# ChairControlInterceptor.net
KiCad netlist of a schematic drawn in EAGLE
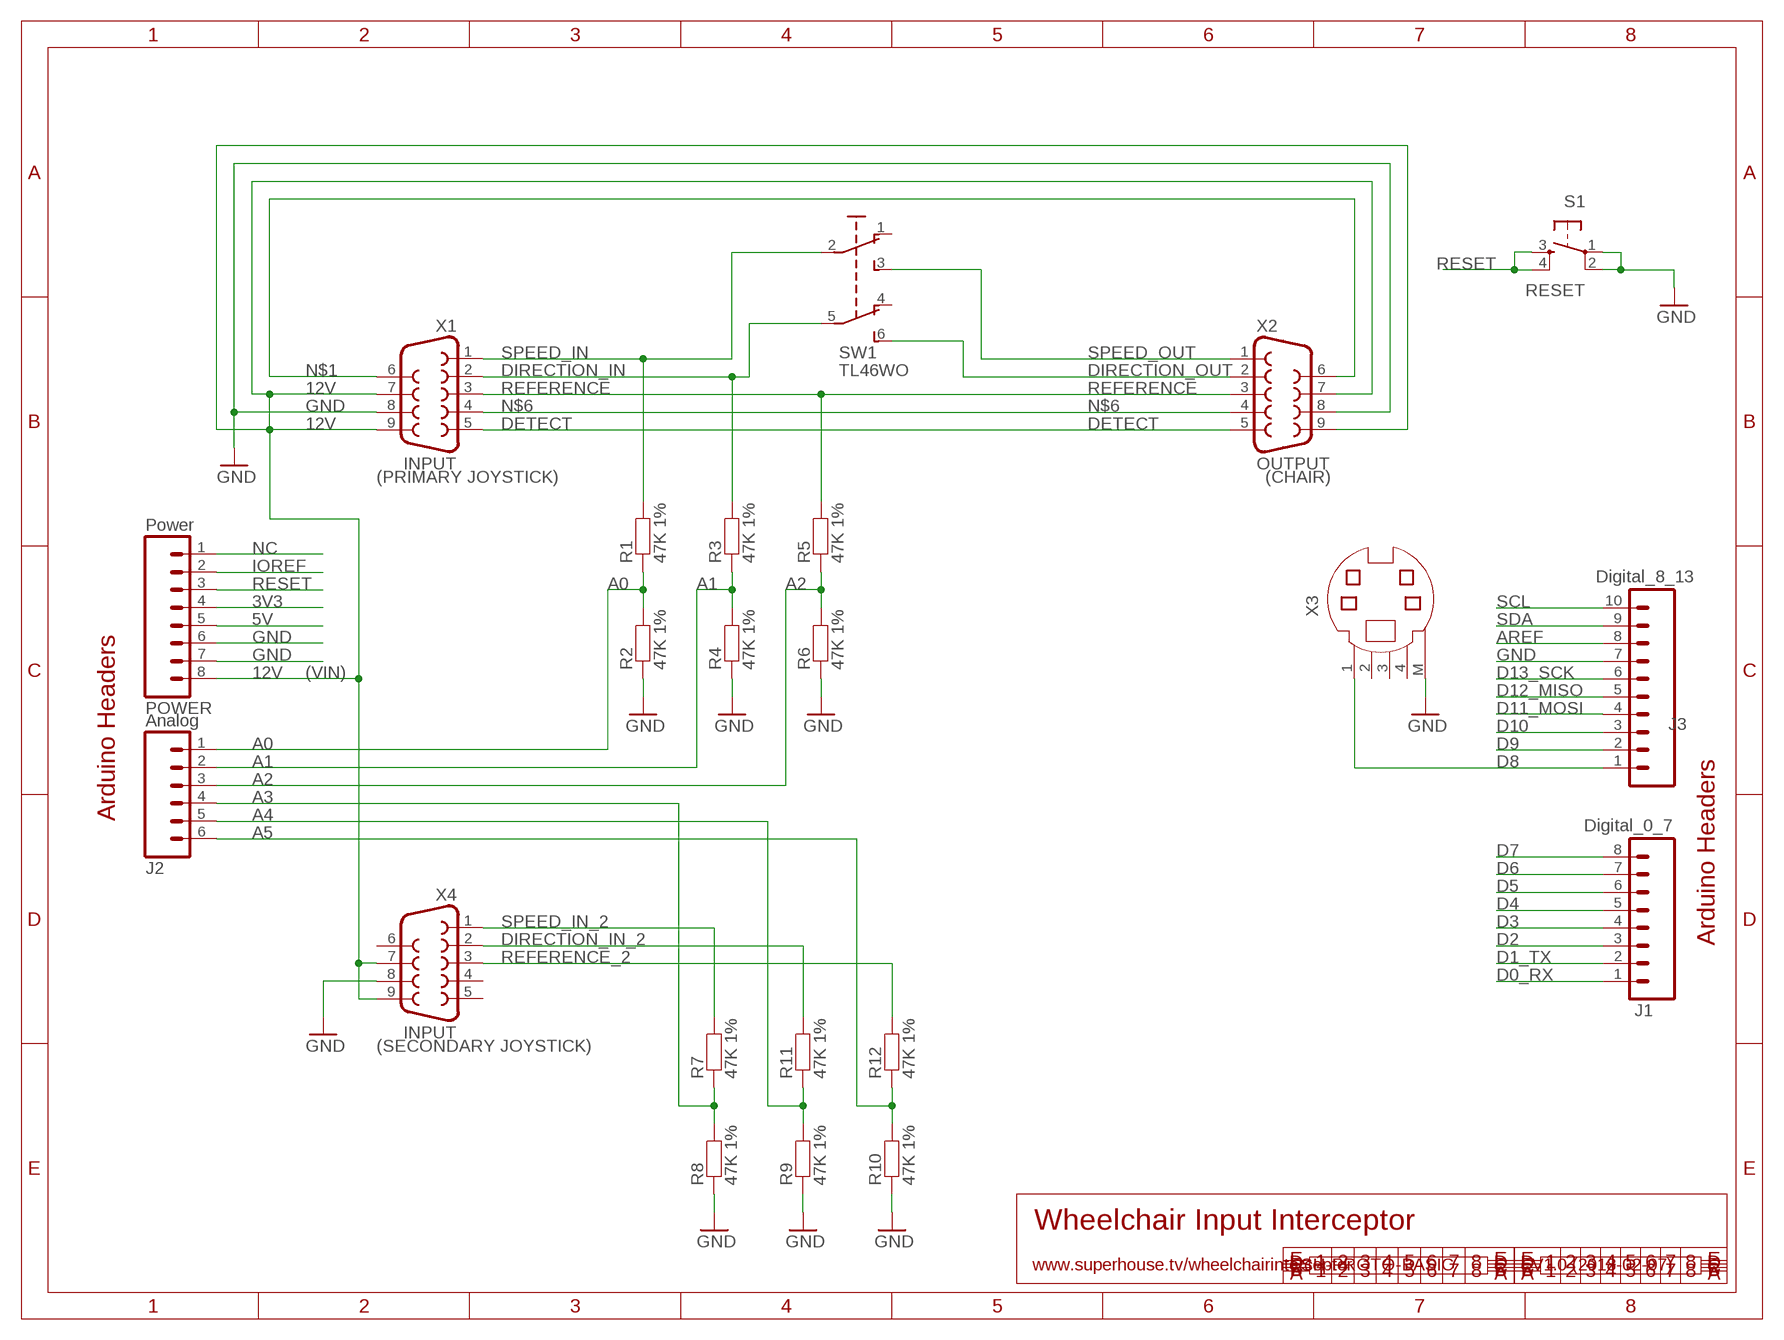
[diagram p0: schematic, sheet 1]

(export (version "E")
  (design (tool "Eeschema 10.0.6"))
  (components
    (comp (ref "J1")
      (value "Digital_0_7")
      (footprint "eagle-import:1X08")
      (libsource (lib "eagle-import") (part "M08"))
    )
    (comp (ref "J2")
      (value "Analog")
      (footprint "eagle-import:1X06")
      (libsource (lib "eagle-import") (part "M06SIP"))
    )
    (comp (ref "J3")
      (value "Digital_8_13")
      (footprint "eagle-import:1X10")
      (libsource (lib "eagle-import") (part "M100.1"))
    )
    (comp (ref "POWER")
      (value "Power")
      (footprint "eagle-import:1X08")
      (libsource (lib "eagle-import") (part "freetronics-original_M08"))
    )
    (comp (ref "R1")
      (value "47K 1%")
      (footprint "eagle-import:0603")
      (libsource (lib "eagle-import") (part "RESISTOR0603"))
    )
    (comp (ref "R2")
      (value "47K 1%")
      (footprint "eagle-import:0603")
      (libsource (lib "eagle-import") (part "RESISTOR0603"))
    )
    (comp (ref "R3")
      (value "47K 1%")
      (footprint "eagle-import:0603")
      (libsource (lib "eagle-import") (part "RESISTOR0603"))
    )
    (comp (ref "R4")
      (value "47K 1%")
      (footprint "eagle-import:0603")
      (libsource (lib "eagle-import") (part "RESISTOR0603"))
    )
    (comp (ref "R5")
      (value "47K 1%")
      (footprint "eagle-import:0603")
      (libsource (lib "eagle-import") (part "RESISTOR0603"))
    )
    (comp (ref "R6")
      (value "47K 1%")
      (footprint "eagle-import:0603")
      (libsource (lib "eagle-import") (part "RESISTOR0603"))
    )
    (comp (ref "R7")
      (value "47K 1%")
      (footprint "eagle-import:0603")
      (libsource (lib "eagle-import") (part "RESISTOR0603"))
    )
    (comp (ref "R8")
      (value "47K 1%")
      (footprint "eagle-import:0603")
      (libsource (lib "eagle-import") (part "RESISTOR0603"))
    )
    (comp (ref "R9")
      (value "47K 1%")
      (footprint "eagle-import:0603")
      (libsource (lib "eagle-import") (part "RESISTOR0603"))
    )
    (comp (ref "R10")
      (value "47K 1%")
      (footprint "eagle-import:0603")
      (libsource (lib "eagle-import") (part "RESISTOR0603"))
    )
    (comp (ref "R11")
      (value "47K 1%")
      (footprint "eagle-import:0603")
      (libsource (lib "eagle-import") (part "RESISTOR0603"))
    )
    (comp (ref "R12")
      (value "47K 1%")
      (footprint "eagle-import:0603")
      (libsource (lib "eagle-import") (part "RESISTOR0603"))
    )
    (comp (ref "S1")
      (value "RESET")
      (footprint "eagle-import:TACTILE-PTH")
      (libsource (lib "eagle-import") (part "TAC_SWITCHPTH"))
    )
    (comp (ref "SW1")
      (value "TL46WO")
      (footprint "eagle-import:TL4XWO")
      (libsource (lib "eagle-import") (part "TL46WO"))
    )
    (comp (ref "X1")
      (value "INPUT")
      (footprint "eagle-import:DB9_MALE")
      (libsource (lib "eagle-import") (part "DB9MALE"))
    )
    (comp (ref "X2")
      (value "OUTPUT")
      (footprint "eagle-import:DB9")
      (libsource (lib "eagle-import") (part "DB9FEMALE"))
    )
    (comp (ref "X3")
      (value "MD04S")
      (footprint "eagle-import:MDIN04S")
      (libsource (lib "eagle-import") (part "MD04S"))
    )
    (comp (ref "X4")
      (value "INPUT")
      (footprint "eagle-import:DB9_MALE")
      (libsource (lib "eagle-import") (part "DB9MALE"))
    )
  )
  (nets
    (net (code "1") (name "/3V3") (class "Default")
      (node (ref "POWER") (pin "4") (pinfunction "4_4") (pintype "passive"))
    )
    (net (code "2") (name "/5V") (class "Default")
      (node (ref "POWER") (pin "5") (pinfunction "5_5") (pintype "passive"))
    )
    (net (code "3") (name "/12V") (class "Default")
      (node (ref "POWER") (pin "8") (pinfunction "8_8") (pintype "passive"))
      (node (ref "X1") (pin "7") (pinfunction "7_7") (pintype "passive"))
      (node (ref "X1") (pin "9") (pinfunction "9_9") (pintype "passive"))
      (node (ref "X2") (pin "7") (pinfunction "7_7") (pintype "passive"))
      (node (ref "X2") (pin "9") (pinfunction "9_9") (pintype "passive"))
      (node (ref "X4") (pin "7") (pinfunction "7_7") (pintype "passive"))
      (node (ref "X4") (pin "9") (pinfunction "9_9") (pintype "passive"))
    )
    (net (code "4") (name "/A0") (class "Default")
      (node (ref "J2") (pin "1") (pinfunction "1_1") (pintype "passive"))
      (node (ref "R1") (pin "1") (pinfunction "1_1") (pintype "passive"))
      (node (ref "R2") (pin "2") (pinfunction "2_2") (pintype "passive"))
    )
    (net (code "5") (name "/A1") (class "Default")
      (node (ref "J2") (pin "2") (pinfunction "2_2") (pintype "passive"))
      (node (ref "R3") (pin "1") (pinfunction "1_1") (pintype "passive"))
      (node (ref "R4") (pin "2") (pinfunction "2_2") (pintype "passive"))
    )
    (net (code "6") (name "/A2") (class "Default")
      (node (ref "J2") (pin "3") (pinfunction "3_3") (pintype "passive"))
      (node (ref "R5") (pin "1") (pinfunction "1_1") (pintype "passive"))
      (node (ref "R6") (pin "2") (pinfunction "2_2") (pintype "passive"))
    )
    (net (code "7") (name "/A3") (class "Default")
      (node (ref "J2") (pin "4") (pinfunction "4_4") (pintype "passive"))
      (node (ref "R7") (pin "1") (pinfunction "1_1") (pintype "passive"))
      (node (ref "R8") (pin "2") (pinfunction "2_2") (pintype "passive"))
    )
    (net (code "8") (name "/A4") (class "Default")
      (node (ref "J2") (pin "5") (pinfunction "5_5") (pintype "passive"))
      (node (ref "R11") (pin "1") (pinfunction "1_1") (pintype "passive"))
      (node (ref "R9") (pin "2") (pinfunction "2_2") (pintype "passive"))
    )
    (net (code "9") (name "/A5") (class "Default")
      (node (ref "J2") (pin "6") (pinfunction "6_6") (pintype "passive"))
      (node (ref "R10") (pin "2") (pinfunction "2_2") (pintype "passive"))
      (node (ref "R12") (pin "1") (pinfunction "1_1") (pintype "passive"))
    )
    (net (code "10") (name "/AREF") (class "Default")
      (node (ref "J3") (pin "8") (pinfunction "8_8") (pintype "passive"))
    )
    (net (code "11") (name "/D0_RX") (class "Default")
      (node (ref "J1") (pin "1") (pinfunction "1_1") (pintype "passive"))
    )
    (net (code "12") (name "/D1_TX") (class "Default")
      (node (ref "J1") (pin "2") (pinfunction "2_2") (pintype "passive"))
    )
    (net (code "13") (name "/D2") (class "Default")
      (node (ref "J1") (pin "3") (pinfunction "3_3") (pintype "passive"))
    )
    (net (code "14") (name "/D3") (class "Default")
      (node (ref "J1") (pin "4") (pinfunction "4_4") (pintype "passive"))
    )
    (net (code "15") (name "/D4") (class "Default")
      (node (ref "J1") (pin "5") (pinfunction "5_5") (pintype "passive"))
    )
    (net (code "16") (name "/D5") (class "Default")
      (node (ref "J1") (pin "6") (pinfunction "6_6") (pintype "passive"))
    )
    (net (code "17") (name "/D6") (class "Default")
      (node (ref "J1") (pin "7") (pinfunction "7_7") (pintype "passive"))
    )
    (net (code "18") (name "/D7") (class "Default")
      (node (ref "J1") (pin "8") (pinfunction "8_8") (pintype "passive"))
    )
    (net (code "19") (name "/D8") (class "Default")
      (node (ref "J3") (pin "1") (pinfunction "1_1") (pintype "passive"))
      (node (ref "X3") (pin "1") (pinfunction "1_1") (pintype "passive"))
    )
    (net (code "20") (name "/D9") (class "Default")
      (node (ref "J3") (pin "2") (pinfunction "2_2") (pintype "passive"))
    )
    (net (code "21") (name "/D10") (class "Default")
      (node (ref "J3") (pin "3") (pinfunction "3_3") (pintype "passive"))
    )
    (net (code "22") (name "/D11_MOSI") (class "Default")
      (node (ref "J3") (pin "4") (pinfunction "4_4") (pintype "passive"))
    )
    (net (code "23") (name "/D12_MISO") (class "Default")
      (node (ref "J3") (pin "5") (pinfunction "5_5") (pintype "passive"))
    )
    (net (code "24") (name "/D13_SCK") (class "Default")
      (node (ref "J3") (pin "6") (pinfunction "6_6") (pintype "passive"))
    )
    (net (code "25") (name "/DETECT") (class "Default")
      (node (ref "X1") (pin "5") (pinfunction "5_5") (pintype "passive"))
      (node (ref "X2") (pin "5") (pinfunction "5_5") (pintype "passive"))
    )
    (net (code "26") (name "/DIRECTION_IN") (class "Default")
      (node (ref "R3") (pin "2") (pinfunction "2_2") (pintype "passive"))
      (node (ref "SW1") (pin "5") (pinfunction "P1_5") (pintype "passive"))
      (node (ref "X1") (pin "2") (pinfunction "2_2") (pintype "passive"))
    )
    (net (code "27") (name "/DIRECTION_IN_2") (class "Default")
      (node (ref "R11") (pin "2") (pinfunction "2_2") (pintype "passive"))
      (node (ref "X4") (pin "2") (pinfunction "2_2") (pintype "passive"))
    )
    (net (code "28") (name "/DIRECTION_OUT") (class "Default")
      (node (ref "SW1") (pin "6") (pinfunction "S1_6") (pintype "passive"))
      (node (ref "X2") (pin "2") (pinfunction "2_2") (pintype "passive"))
    )
    (net (code "29") (name "/IOREF") (class "Default")
      (node (ref "POWER") (pin "2") (pinfunction "2_2") (pintype "passive"))
    )
    (net (code "30") (name "/N$1") (class "Default")
      (node (ref "X1") (pin "6") (pinfunction "6_6") (pintype "passive"))
      (node (ref "X2") (pin "6") (pinfunction "6_6") (pintype "passive"))
    )
    (net (code "31") (name "/N$6") (class "Default")
      (node (ref "X1") (pin "4") (pinfunction "4_4") (pintype "passive"))
      (node (ref "X2") (pin "4") (pinfunction "4_4") (pintype "passive"))
    )
    (net (code "32") (name "/NC") (class "Default")
      (node (ref "POWER") (pin "1") (pinfunction "1_1") (pintype "passive"))
    )
    (net (code "33") (name "/REFERENCE") (class "Default")
      (node (ref "R5") (pin "2") (pinfunction "2_2") (pintype "passive"))
      (node (ref "X1") (pin "3") (pinfunction "3_3") (pintype "passive"))
      (node (ref "X2") (pin "3") (pinfunction "3_3") (pintype "passive"))
    )
    (net (code "34") (name "/REFERENCE_2") (class "Default")
      (node (ref "R12") (pin "2") (pinfunction "2_2") (pintype "passive"))
      (node (ref "X4") (pin "3") (pinfunction "3_3") (pintype "passive"))
    )
    (net (code "35") (name "/RESET") (class "Default")
      (node (ref "POWER") (pin "3") (pinfunction "3_3") (pintype "passive"))
      (node (ref "S1") (pin "3") (pinfunction "3_3") (pintype "passive"))
      (node (ref "S1") (pin "4") (pinfunction "4_4") (pintype "passive"))
    )
    (net (code "36") (name "/SCL") (class "Default")
      (node (ref "J3") (pin "10") (pinfunction "10_10") (pintype "passive"))
    )
    (net (code "37") (name "/SDA") (class "Default")
      (node (ref "J3") (pin "9") (pinfunction "9_9") (pintype "passive"))
    )
    (net (code "38") (name "/SPEED_IN") (class "Default")
      (node (ref "R1") (pin "2") (pinfunction "2_2") (pintype "passive"))
      (node (ref "SW1") (pin "2") (pinfunction "P_2") (pintype "passive"))
      (node (ref "X1") (pin "1") (pinfunction "1_1") (pintype "passive"))
    )
    (net (code "39") (name "/SPEED_IN_2") (class "Default")
      (node (ref "R7") (pin "2") (pinfunction "2_2") (pintype "passive"))
      (node (ref "X4") (pin "1") (pinfunction "1_1") (pintype "passive"))
    )
    (net (code "40") (name "/SPEED_OUT") (class "Default")
      (node (ref "SW1") (pin "3") (pinfunction "S_3") (pintype "passive"))
      (node (ref "X2") (pin "1") (pinfunction "1_1") (pintype "passive"))
    )
    (net (code "41") (name "GND") (class "Default")
      (node (ref "J3") (pin "7") (pinfunction "7_7") (pintype "passive"))
      (node (ref "POWER") (pin "6") (pinfunction "6_6") (pintype "passive"))
      (node (ref "POWER") (pin "7") (pinfunction "7_7") (pintype "passive"))
      (node (ref "R10") (pin "1") (pinfunction "1_1") (pintype "passive"))
      (node (ref "R2") (pin "1") (pinfunction "1_1") (pintype "passive"))
      (node (ref "R4") (pin "1") (pinfunction "1_1") (pintype "passive"))
      (node (ref "R6") (pin "1") (pinfunction "1_1") (pintype "passive"))
      (node (ref "R8") (pin "1") (pinfunction "1_1") (pintype "passive"))
      (node (ref "R9") (pin "1") (pinfunction "1_1") (pintype "passive"))
      (node (ref "S1") (pin "1") (pinfunction "1_1") (pintype "passive"))
      (node (ref "S1") (pin "2") (pinfunction "2_2") (pintype "passive"))
      (node (ref "X1") (pin "8") (pinfunction "8_8") (pintype "passive"))
      (node (ref "X2") (pin "8") (pinfunction "8_8") (pintype "passive"))
      (node (ref "X3") (pin "M") (pinfunction "5_M") (pintype "passive"))
      (node (ref "X4") (pin "8") (pinfunction "8_8") (pintype "passive"))
    )
    (net (code "42") (name "unconnected-(SW1-O-Pad1)") (class "Default")
      (node (ref "SW1") (pin "1") (pinfunction "O_1") (pintype "passive"))
    )
    (net (code "43") (name "unconnected-(SW1-O1-Pad4)") (class "Default")
      (node (ref "SW1") (pin "4") (pinfunction "O1_4") (pintype "passive"))
    )
    (net (code "44") (name "unconnected-(X3-Pad2)") (class "Default")
      (node (ref "X3") (pin "2") (pinfunction "2_2") (pintype "passive"))
    )
    (net (code "45") (name "unconnected-(X3-Pad3)") (class "Default")
      (node (ref "X3") (pin "3") (pinfunction "3_3") (pintype "passive"))
    )
    (net (code "46") (name "unconnected-(X3-Pad4)") (class "Default")
      (node (ref "X3") (pin "4") (pinfunction "4_4") (pintype "passive"))
    )
    (net (code "47") (name "unconnected-(X4-Pad4)") (class "Default")
      (node (ref "X4") (pin "4") (pinfunction "4_4") (pintype "passive"))
    )
    (net (code "48") (name "unconnected-(X4-Pad5)") (class "Default")
      (node (ref "X4") (pin "5") (pinfunction "5_5") (pintype "passive"))
    )
    (net (code "49") (name "unconnected-(X4-Pad6)") (class "Default")
      (node (ref "X4") (pin "6") (pinfunction "6_6") (pintype "passive"))
    )
  )
)
